# Sheet2.net
KiCad netlist of a schematic drawn in Altium Designer
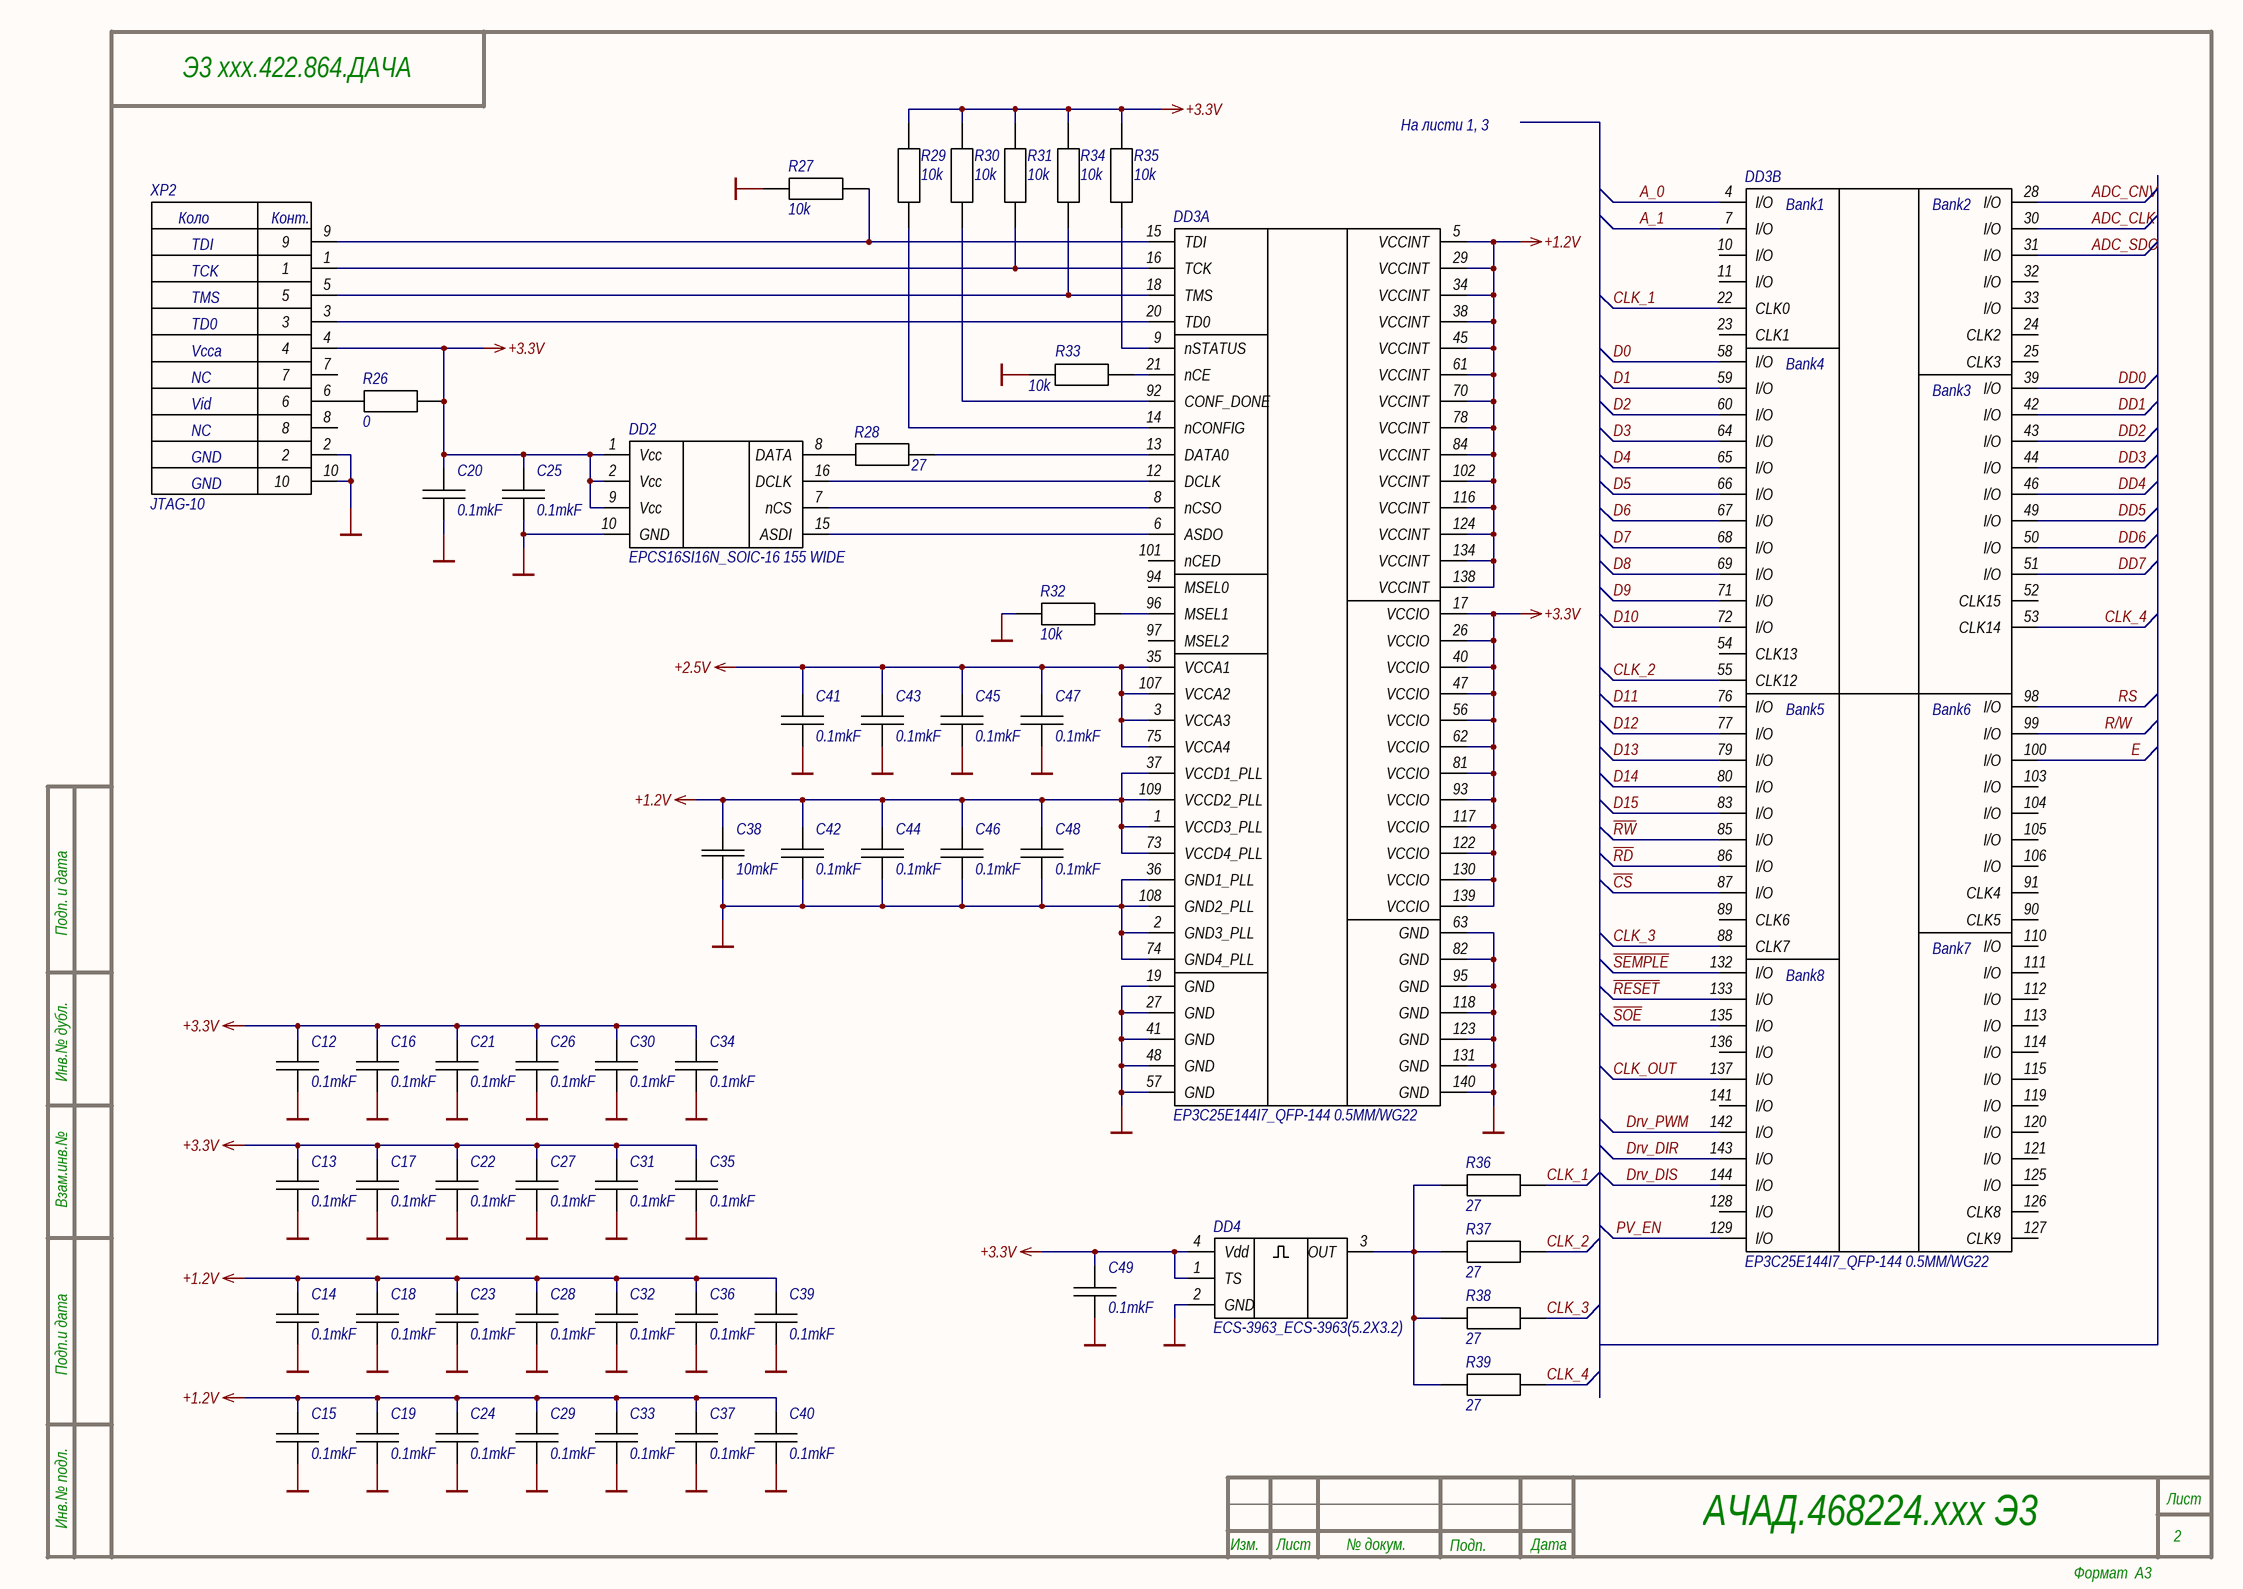
[diagram p0: Sheet2.SchDoc]

(export (version "E")
  (design (tool "Eeschema 10.0.6"))
  (components
    (comp (ref "C12")
      (value "0.1mkF")
      (footprint "C_0603")
      (description "C_0.1mkF_0603")
      (libsource (lib "АСК_1") (part "C_0.1mkF_0603"))
    )
    (comp (ref "C13")
      (value "0.1mkF")
      (footprint "C_0603")
      (description "C_0.1mkF_0603")
      (libsource (lib "АСК_1") (part "C_0.1mkF_0603"))
    )
    (comp (ref "C14")
      (value "0.1mkF")
      (footprint "C_0603")
      (description "C_0.1mkF_0603")
      (libsource (lib "АСК_1") (part "C_0.1mkF_0603"))
    )
    (comp (ref "C15")
      (value "0.1mkF")
      (footprint "C_0603")
      (description "C_0.1mkF_0603")
      (libsource (lib "АСК_1") (part "C_0.1mkF_0603"))
    )
    (comp (ref "C16")
      (value "0.1mkF")
      (footprint "C_0603")
      (description "C_0.1mkF_0603")
      (libsource (lib "АСК_1") (part "C_0.1mkF_0603"))
    )
    (comp (ref "C17")
      (value "0.1mkF")
      (footprint "C_0603")
      (description "C_0.1mkF_0603")
      (libsource (lib "АСК_1") (part "C_0.1mkF_0603"))
    )
    (comp (ref "C18")
      (value "0.1mkF")
      (footprint "C_0603")
      (description "C_0.1mkF_0603")
      (libsource (lib "АСК_1") (part "C_0.1mkF_0603"))
    )
    (comp (ref "C19")
      (value "0.1mkF")
      (footprint "C_0603")
      (description "C_0.1mkF_0603")
      (libsource (lib "АСК_1") (part "C_0.1mkF_0603"))
    )
    (comp (ref "C20")
      (value "0.1mkF")
      (footprint "C_0603")
      (description "C_0.1mkF_0603")
      (libsource (lib "АСК_1") (part "C_0.1mkF_0603"))
    )
    (comp (ref "C21")
      (value "0.1mkF")
      (footprint "C_0603")
      (description "C_0.1mkF_0603")
      (libsource (lib "АСК_1") (part "C_0.1mkF_0603"))
    )
    (comp (ref "C22")
      (value "0.1mkF")
      (footprint "C_0603")
      (description "C_0.1mkF_0603")
      (libsource (lib "АСК_1") (part "C_0.1mkF_0603"))
    )
    (comp (ref "C23")
      (value "0.1mkF")
      (footprint "C_0603")
      (description "C_0.1mkF_0603")
      (libsource (lib "АСК_1") (part "C_0.1mkF_0603"))
    )
    (comp (ref "C24")
      (value "0.1mkF")
      (footprint "C_0603")
      (description "C_0.1mkF_0603")
      (libsource (lib "АСК_1") (part "C_0.1mkF_0603"))
    )
    (comp (ref "C25")
      (value "0.1mkF")
      (footprint "C_0603")
      (description "C_0.1mkF_0603")
      (libsource (lib "АСК_1") (part "C_0.1mkF_0603"))
    )
    (comp (ref "C26")
      (value "0.1mkF")
      (footprint "C_0603")
      (description "C_0.1mkF_0603")
      (libsource (lib "АСК_1") (part "C_0.1mkF_0603"))
    )
    (comp (ref "C27")
      (value "0.1mkF")
      (footprint "C_0603")
      (description "C_0.1mkF_0603")
      (libsource (lib "АСК_1") (part "C_0.1mkF_0603"))
    )
    (comp (ref "C28")
      (value "0.1mkF")
      (footprint "C_0603")
      (description "C_0.1mkF_0603")
      (libsource (lib "АСК_1") (part "C_0.1mkF_0603"))
    )
    (comp (ref "C29")
      (value "0.1mkF")
      (footprint "C_0603")
      (description "C_0.1mkF_0603")
      (libsource (lib "АСК_1") (part "C_0.1mkF_0603"))
    )
    (comp (ref "C30")
      (value "0.1mkF")
      (footprint "C_0603")
      (description "C_0.1mkF_0603")
      (libsource (lib "АСК_1") (part "C_0.1mkF_0603"))
    )
    (comp (ref "C31")
      (value "0.1mkF")
      (footprint "C_0603")
      (description "C_0.1mkF_0603")
      (libsource (lib "АСК_1") (part "C_0.1mkF_0603"))
    )
    (comp (ref "C32")
      (value "0.1mkF")
      (footprint "C_0603")
      (description "C_0.1mkF_0603")
      (libsource (lib "АСК_1") (part "C_0.1mkF_0603"))
    )
    (comp (ref "C33")
      (value "0.1mkF")
      (footprint "C_0603")
      (description "C_0.1mkF_0603")
      (libsource (lib "АСК_1") (part "C_0.1mkF_0603"))
    )
    (comp (ref "C34")
      (value "0.1mkF")
      (footprint "C_0603")
      (description "C_0.1mkF_0603")
      (libsource (lib "АСК_1") (part "C_0.1mkF_0603"))
    )
    (comp (ref "C35")
      (value "0.1mkF")
      (footprint "C_0603")
      (description "C_0.1mkF_0603")
      (libsource (lib "АСК_1") (part "C_0.1mkF_0603"))
    )
    (comp (ref "C36")
      (value "0.1mkF")
      (footprint "C_0603")
      (description "C_0.1mkF_0603")
      (libsource (lib "АСК_1") (part "C_0.1mkF_0603"))
    )
    (comp (ref "C37")
      (value "0.1mkF")
      (footprint "C_0603")
      (description "C_0.1mkF_0603")
      (libsource (lib "АСК_1") (part "C_0.1mkF_0603"))
    )
    (comp (ref "C38")
      (value "10mkF")
      (footprint "C_1206")
      (description "C_10mkF_1206")
      (libsource (lib "АСК_1") (part "C_10mkF_1206"))
    )
    (comp (ref "C39")
      (value "0.1mkF")
      (footprint "C_0603")
      (description "C_0.1mkF_0603")
      (libsource (lib "АСК_1") (part "C_0.1mkF_0603"))
    )
    (comp (ref "C40")
      (value "0.1mkF")
      (footprint "C_0603")
      (description "C_0.1mkF_0603")
      (libsource (lib "АСК_1") (part "C_0.1mkF_0603"))
    )
    (comp (ref "C41")
      (value "0.1mkF")
      (footprint "C_0603")
      (description "C_0.1mkF_0603")
      (libsource (lib "АСК_1") (part "C_0.1mkF_0603"))
    )
    (comp (ref "C42")
      (value "0.1mkF")
      (footprint "C_0603")
      (description "C_0.1mkF_0603")
      (libsource (lib "АСК_1") (part "C_0.1mkF_0603"))
    )
    (comp (ref "C43")
      (value "0.1mkF")
      (footprint "C_0603")
      (description "C_0.1mkF_0603")
      (libsource (lib "АСК_1") (part "C_0.1mkF_0603"))
    )
    (comp (ref "C44")
      (value "0.1mkF")
      (footprint "C_0603")
      (description "C_0.1mkF_0603")
      (libsource (lib "АСК_1") (part "C_0.1mkF_0603"))
    )
    (comp (ref "C45")
      (value "0.1mkF")
      (footprint "C_0603")
      (description "C_0.1mkF_0603")
      (libsource (lib "АСК_1") (part "C_0.1mkF_0603"))
    )
    (comp (ref "C46")
      (value "0.1mkF")
      (footprint "C_0603")
      (description "C_0.1mkF_0603")
      (libsource (lib "АСК_1") (part "C_0.1mkF_0603"))
    )
    (comp (ref "C47")
      (value "0.1mkF")
      (footprint "C_0603")
      (description "C_0.1mkF_0603")
      (libsource (lib "АСК_1") (part "C_0.1mkF_0603"))
    )
    (comp (ref "C48")
      (value "0.1mkF")
      (footprint "C_0603")
      (description "C_0.1mkF_0603")
      (libsource (lib "АСК_1") (part "C_0.1mkF_0603"))
    )
    (comp (ref "C49")
      (value "0.1mkF")
      (footprint "C_0603")
      (description "C_0.1mkF_0603")
      (libsource (lib "АСК_1") (part "C_0.1mkF_0603"))
    )
    (comp (ref "DD2")
      (value "EPCS16SI16N_SOIC-16 155 WIDE")
      (footprint "SOIC127P600X175-16N")
      (libsource (lib "АСК_1") (part "EPCS16SI16N_SOIC-16 155 WIDE"))
    )
    (comp (ref "DD3")
      (value "EP3C25E144I7_QFP-144 0.5MM/WG22")
      (footprint "QFP65P3122X3122X395-144N")
      (libsource (lib "АСК_1") (part "EP3C25E144I7_QFP-144 0.5MM/WG22"))
    )
    (comp (ref "DD4")
      (value "ECS-3963_ECS-3963(5.2X3.2)")
      (footprint "ECS-3961")
      (libsource (lib "АСК_1") (part "ECS-3963_ECS-3963(5.2X3.2)"))
    )
    (comp (ref "R26")
      (value "0")
      (footprint "R_1206")
      (description "R_10_1206")
      (libsource (lib "АСК_1") (part "R_10_1206"))
    )
    (comp (ref "R27")
      (value "10k")
      (footprint "R_0603")
      (description "R_10k_0603")
      (libsource (lib "АСК_1") (part "R_10k_0603"))
    )
    (comp (ref "R28")
      (value "27")
      (footprint "R_1206")
      (description "R_10_1206")
      (libsource (lib "АСК_1") (part "R_10_1206"))
    )
    (comp (ref "R29")
      (value "10k")
      (footprint "R_0603")
      (description "R_10k_0603")
      (libsource (lib "АСК_1") (part "R_10k_0603"))
    )
    (comp (ref "R30")
      (value "10k")
      (footprint "R_0603")
      (description "R_10k_0603")
      (libsource (lib "АСК_1") (part "R_10k_0603"))
    )
    (comp (ref "R31")
      (value "10k")
      (footprint "R_0603")
      (description "R_10k_0603")
      (libsource (lib "АСК_1") (part "R_10k_0603"))
    )
    (comp (ref "R32")
      (value "10k")
      (footprint "R_0603")
      (description "R_10k_0603")
      (libsource (lib "АСК_1") (part "R_10k_0603"))
    )
    (comp (ref "R33")
      (value "10k")
      (footprint "R_0603")
      (description "R_10k_0603")
      (libsource (lib "АСК_1") (part "R_10k_0603"))
    )
    (comp (ref "R34")
      (value "10k")
      (footprint "R_0603")
      (description "R_10k_0603")
      (libsource (lib "АСК_1") (part "R_10k_0603"))
    )
    (comp (ref "R35")
      (value "10k")
      (footprint "R_0603")
      (description "R_10k_0603")
      (libsource (lib "АСК_1") (part "R_10k_0603"))
    )
    (comp (ref "R36")
      (value "27")
      (footprint "R_0603")
      (description "R_10k_0603")
      (libsource (lib "АСК_1") (part "R_10k_0603"))
    )
    (comp (ref "R37")
      (value "27")
      (footprint "R_0603")
      (description "R_10k_0603")
      (libsource (lib "АСК_1") (part "R_10k_0603"))
    )
    (comp (ref "R38")
      (value "27")
      (footprint "R_0603")
      (description "R_10k_0603")
      (libsource (lib "АСК_1") (part "R_10k_0603"))
    )
    (comp (ref "R39")
      (value "27")
      (footprint "R_0603")
      (description "R_10k_0603")
      (libsource (lib "АСК_1") (part "R_10k_0603"))
    )
    (comp (ref "XP2") (value "JTAG-10") (libsource (lib "АСК_1") (part "JTAG-10")))
  )
  (nets
    (net (code "1") (name "+1.2V") (class "Default")
      (node (ref "C14") (pin "2") (pinfunction "2_2") (pintype "passive"))
      (node (ref "C15") (pin "2") (pinfunction "2_2") (pintype "passive"))
      (node (ref "C18") (pin "2") (pinfunction "2_2") (pintype "passive"))
      (node (ref "C19") (pin "2") (pinfunction "2_2") (pintype "passive"))
      (node (ref "C23") (pin "2") (pinfunction "2_2") (pintype "passive"))
      (node (ref "C24") (pin "2") (pinfunction "2_2") (pintype "passive"))
      (node (ref "C28") (pin "2") (pinfunction "2_2") (pintype "passive"))
      (node (ref "C29") (pin "2") (pinfunction "2_2") (pintype "passive"))
      (node (ref "C32") (pin "2") (pinfunction "2_2") (pintype "passive"))
      (node (ref "C33") (pin "2") (pinfunction "2_2") (pintype "passive"))
      (node (ref "C36") (pin "2") (pinfunction "2_2") (pintype "passive"))
      (node (ref "C37") (pin "2") (pinfunction "2_2") (pintype "passive"))
      (node (ref "C38") (pin "2") (pinfunction "2_2") (pintype "passive"))
      (node (ref "C39") (pin "2") (pinfunction "2_2") (pintype "passive"))
      (node (ref "C40") (pin "2") (pinfunction "2_2") (pintype "passive"))
      (node (ref "C42") (pin "2") (pinfunction "2_2") (pintype "passive"))
      (node (ref "C44") (pin "2") (pinfunction "2_2") (pintype "passive"))
      (node (ref "C46") (pin "2") (pinfunction "2_2") (pintype "passive"))
      (node (ref "C48") (pin "2") (pinfunction "2_2") (pintype "passive"))
      (node (ref "DD3") (pin "1") (pinfunction "VCCD3_PLL_1") (pintype "passive"))
      (node (ref "DD3") (pin "102") (pinfunction "VCCINT_102") (pintype "passive"))
      (node (ref "DD3") (pin "109") (pinfunction "VCCD2_PLL_109") (pintype "passive"))
      (node (ref "DD3") (pin "116") (pinfunction "VCCINT_116") (pintype "passive"))
      (node (ref "DD3") (pin "124") (pinfunction "VCCINT_124") (pintype "passive"))
      (node (ref "DD3") (pin "134") (pinfunction "VCCINT_134") (pintype "passive"))
      (node (ref "DD3") (pin "138") (pinfunction "VCCINT_138") (pintype "passive"))
      (node (ref "DD3") (pin "29") (pinfunction "VCCINT_29") (pintype "passive"))
      (node (ref "DD3") (pin "34") (pinfunction "VCCINT_34") (pintype "passive"))
      (node (ref "DD3") (pin "37") (pinfunction "VCCD1_PLL_37") (pintype "passive"))
      (node (ref "DD3") (pin "38") (pinfunction "VCCINT_38") (pintype "passive"))
      (node (ref "DD3") (pin "45") (pinfunction "VCCINT_45") (pintype "passive"))
      (node (ref "DD3") (pin "5") (pinfunction "VCCINT_5") (pintype "passive"))
      (node (ref "DD3") (pin "61") (pinfunction "VCCINT_61") (pintype "passive"))
      (node (ref "DD3") (pin "70") (pinfunction "VCCINT_70") (pintype "passive"))
      (node (ref "DD3") (pin "73") (pinfunction "VCCD4_PLL_73") (pintype "passive"))
      (node (ref "DD3") (pin "78") (pinfunction "VCCINT_78") (pintype "passive"))
      (node (ref "DD3") (pin "84") (pinfunction "VCCINT_84") (pintype "passive"))
    )
    (net (code "2") (name "+2.5V") (class "Default")
      (node (ref "C41") (pin "2") (pinfunction "2_2") (pintype "passive"))
      (node (ref "C43") (pin "2") (pinfunction "2_2") (pintype "passive"))
      (node (ref "C45") (pin "2") (pinfunction "2_2") (pintype "passive"))
      (node (ref "C47") (pin "2") (pinfunction "2_2") (pintype "passive"))
      (node (ref "DD3") (pin "107") (pinfunction "VCCA2_107") (pintype "passive"))
      (node (ref "DD3") (pin "3") (pinfunction "VCCA3_3") (pintype "passive"))
      (node (ref "DD3") (pin "35") (pinfunction "VCCA1_35") (pintype "passive"))
      (node (ref "DD3") (pin "75") (pinfunction "VCCA4_75") (pintype "passive"))
    )
    (net (code "3") (name "+3.3V") (class "Default")
      (node (ref "C12") (pin "2") (pinfunction "2_2") (pintype "passive"))
      (node (ref "C13") (pin "2") (pinfunction "2_2") (pintype "passive"))
      (node (ref "C16") (pin "2") (pinfunction "2_2") (pintype "passive"))
      (node (ref "C17") (pin "2") (pinfunction "2_2") (pintype "passive"))
      (node (ref "C20") (pin "2") (pinfunction "2_2") (pintype "passive"))
      (node (ref "C21") (pin "2") (pinfunction "2_2") (pintype "passive"))
      (node (ref "C22") (pin "2") (pinfunction "2_2") (pintype "passive"))
      (node (ref "C25") (pin "2") (pinfunction "2_2") (pintype "passive"))
      (node (ref "C26") (pin "2") (pinfunction "2_2") (pintype "passive"))
      (node (ref "C27") (pin "2") (pinfunction "2_2") (pintype "passive"))
      (node (ref "C30") (pin "2") (pinfunction "2_2") (pintype "passive"))
      (node (ref "C31") (pin "2") (pinfunction "2_2") (pintype "passive"))
      (node (ref "C34") (pin "2") (pinfunction "2_2") (pintype "passive"))
      (node (ref "C35") (pin "2") (pinfunction "2_2") (pintype "passive"))
      (node (ref "C49") (pin "2") (pinfunction "2_2") (pintype "passive"))
      (node (ref "DD2") (pin "1") (pinfunction "Vcc_1") (pintype "passive"))
      (node (ref "DD2") (pin "2") (pinfunction "Vcc_2") (pintype "passive"))
      (node (ref "DD2") (pin "9") (pinfunction "Vcc_9") (pintype "passive"))
      (node (ref "DD3") (pin "117") (pinfunction "VCCIO_117") (pintype "passive"))
      (node (ref "DD3") (pin "122") (pinfunction "VCCIO_122") (pintype "passive"))
      (node (ref "DD3") (pin "130") (pinfunction "VCCIO_130") (pintype "passive"))
      (node (ref "DD3") (pin "139") (pinfunction "VCCIO_139") (pintype "passive"))
      (node (ref "DD3") (pin "17") (pinfunction "VCCIO_17") (pintype "passive"))
      (node (ref "DD3") (pin "26") (pinfunction "VCCIO_26") (pintype "passive"))
      (node (ref "DD3") (pin "40") (pinfunction "VCCIO_40") (pintype "passive"))
      (node (ref "DD3") (pin "47") (pinfunction "VCCIO_47") (pintype "passive"))
      (node (ref "DD3") (pin "56") (pinfunction "VCCIO_56") (pintype "passive"))
      (node (ref "DD3") (pin "62") (pinfunction "VCCIO_62") (pintype "passive"))
      (node (ref "DD3") (pin "81") (pinfunction "VCCIO_81") (pintype "passive"))
      (node (ref "DD3") (pin "93") (pinfunction "VCCIO_93") (pintype "passive"))
      (node (ref "DD4") (pin "1") (pinfunction "TS_1") (pintype "passive"))
      (node (ref "DD4") (pin "4") (pinfunction "Vdd_4") (pintype "passive"))
      (node (ref "R26") (pin "1") (pinfunction "1_1") (pintype "passive"))
      (node (ref "R29") (pin "2") (pinfunction "2_2") (pintype "passive"))
      (node (ref "R30") (pin "2") (pinfunction "2_2") (pintype "passive"))
      (node (ref "R31") (pin "2") (pinfunction "2_2") (pintype "passive"))
      (node (ref "R34") (pin "2") (pinfunction "2_2") (pintype "passive"))
      (node (ref "R35") (pin "2") (pinfunction "2_2") (pintype "passive"))
      (node (ref "XP2") (pin "4") (pinfunction "4_4") (pintype "passive"))
    )
    (net (code "4") (name "/ADC_CLK") (class "Default")
      (node (ref "DD3") (pin "30") (pinfunction "I/O_30") (pintype "passive"))
    )
    (net (code "5") (name "/ADC_CNV") (class "Default")
      (node (ref "DD3") (pin "28") (pinfunction "I/O_28") (pintype "passive"))
    )
    (net (code "6") (name "/ADC_SDO") (class "Default")
      (node (ref "DD3") (pin "31") (pinfunction "I/O_31") (pintype "passive"))
    )
    (net (code "7") (name "/A_0") (class "Default")
      (node (ref "DD3") (pin "4") (pinfunction "I/O_4") (pintype "passive"))
    )
    (net (code "8") (name "/A_1") (class "Default")
      (node (ref "DD3") (pin "7") (pinfunction "I/O_7") (pintype "passive"))
    )
    (net (code "9") (name "/CLK_1") (class "Default")
      (node (ref "DD3") (pin "22") (pinfunction "CLK0_22") (pintype "passive"))
      (node (ref "R36") (pin "2") (pinfunction "2_2") (pintype "passive"))
    )
    (net (code "10") (name "/CLK_2") (class "Default")
      (node (ref "DD3") (pin "55") (pinfunction "CLK12_55") (pintype "passive"))
      (node (ref "R37") (pin "2") (pinfunction "2_2") (pintype "passive"))
    )
    (net (code "11") (name "/CLK_3") (class "Default")
      (node (ref "DD3") (pin "88") (pinfunction "CLK7_88") (pintype "passive"))
      (node (ref "R38") (pin "2") (pinfunction "2_2") (pintype "passive"))
    )
    (net (code "12") (name "/CLK_4") (class "Default")
      (node (ref "DD3") (pin "53") (pinfunction "CLK14_53") (pintype "passive"))
      (node (ref "R39") (pin "2") (pinfunction "2_2") (pintype "passive"))
    )
    (net (code "13") (name "/CLK_OUT") (class "Default")
      (node (ref "DD3") (pin "137") (pinfunction "I/O_137") (pintype "passive"))
    )
    (net (code "14") (name "/D0") (class "Default")
      (node (ref "DD3") (pin "58") (pinfunction "I/O_58") (pintype "passive"))
    )
    (net (code "15") (name "/D1") (class "Default")
      (node (ref "DD3") (pin "59") (pinfunction "I/O_59") (pintype "passive"))
    )
    (net (code "16") (name "/D2") (class "Default")
      (node (ref "DD3") (pin "60") (pinfunction "I/O_60") (pintype "passive"))
    )
    (net (code "17") (name "/D3") (class "Default")
      (node (ref "DD3") (pin "64") (pinfunction "I/O_64") (pintype "passive"))
    )
    (net (code "18") (name "/D4") (class "Default")
      (node (ref "DD3") (pin "65") (pinfunction "I/O_65") (pintype "passive"))
    )
    (net (code "19") (name "/D5") (class "Default")
      (node (ref "DD3") (pin "66") (pinfunction "I/O_66") (pintype "passive"))
    )
    (net (code "20") (name "/D6") (class "Default")
      (node (ref "DD3") (pin "67") (pinfunction "I/O_67") (pintype "passive"))
    )
    (net (code "21") (name "/D7") (class "Default")
      (node (ref "DD3") (pin "68") (pinfunction "I/O_68") (pintype "passive"))
    )
    (net (code "22") (name "/D8") (class "Default")
      (node (ref "DD3") (pin "69") (pinfunction "I/O_69") (pintype "passive"))
    )
    (net (code "23") (name "/D9") (class "Default")
      (node (ref "DD3") (pin "71") (pinfunction "I/O_71") (pintype "passive"))
    )
    (net (code "24") (name "/D10") (class "Default")
      (node (ref "DD3") (pin "72") (pinfunction "I/O_72") (pintype "passive"))
    )
    (net (code "25") (name "/D11") (class "Default")
      (node (ref "DD3") (pin "76") (pinfunction "I/O_76") (pintype "passive"))
    )
    (net (code "26") (name "/D12") (class "Default")
      (node (ref "DD3") (pin "77") (pinfunction "I/O_77") (pintype "passive"))
    )
    (net (code "27") (name "/D13") (class "Default")
      (node (ref "DD3") (pin "79") (pinfunction "I/O_79") (pintype "passive"))
    )
    (net (code "28") (name "/D14") (class "Default")
      (node (ref "DD3") (pin "80") (pinfunction "I/O_80") (pintype "passive"))
    )
    (net (code "29") (name "/D15") (class "Default")
      (node (ref "DD3") (pin "83") (pinfunction "I/O_83") (pintype "passive"))
    )
    (net (code "30") (name "/DD0") (class "Default")
      (node (ref "DD3") (pin "39") (pinfunction "I/O_39") (pintype "passive"))
    )
    (net (code "31") (name "/DD1") (class "Default")
      (node (ref "DD3") (pin "42") (pinfunction "I/O_42") (pintype "passive"))
    )
    (net (code "32") (name "/DD2") (class "Default")
      (node (ref "DD3") (pin "43") (pinfunction "I/O_43") (pintype "passive"))
    )
    (net (code "33") (name "/DD3") (class "Default")
      (node (ref "DD3") (pin "44") (pinfunction "I/O_44") (pintype "passive"))
    )
    (net (code "34") (name "/DD4") (class "Default")
      (node (ref "DD3") (pin "46") (pinfunction "I/O_46") (pintype "passive"))
    )
    (net (code "35") (name "/DD5") (class "Default")
      (node (ref "DD3") (pin "49") (pinfunction "I/O_49") (pintype "passive"))
    )
    (net (code "36") (name "/DD6") (class "Default")
      (node (ref "DD3") (pin "50") (pinfunction "I/O_50") (pintype "passive"))
    )
    (net (code "37") (name "/DD7") (class "Default")
      (node (ref "DD3") (pin "51") (pinfunction "I/O_51") (pintype "passive"))
    )
    (net (code "38") (name "/Drv_DIR") (class "Default")
      (node (ref "DD3") (pin "143") (pinfunction "I/O_143") (pintype "passive"))
    )
    (net (code "39") (name "/Drv_DIS") (class "Default")
      (node (ref "DD3") (pin "144") (pinfunction "I/O_144") (pintype "passive"))
    )
    (net (code "40") (name "/Drv_PWM") (class "Default")
      (node (ref "DD3") (pin "142") (pinfunction "I/O_142") (pintype "passive"))
    )
    (net (code "41") (name "/E") (class "Default")
      (node (ref "DD3") (pin "100") (pinfunction "I/O_100") (pintype "passive"))
    )
    (net (code "42") (name "/PV_EN") (class "Default")
      (node (ref "DD3") (pin "129") (pinfunction "I/O_129") (pintype "passive"))
    )
    (net (code "43") (name "/RS") (class "Default")
      (node (ref "DD3") (pin "98") (pinfunction "I/O_98") (pintype "passive"))
    )
    (net (code "44") (name "/R{slash}W") (class "Default")
      (node (ref "DD3") (pin "99") (pinfunction "I/O_99") (pintype "passive"))
    )
    (net (code "45") (name "/~{CS}") (class "Default")
      (node (ref "DD3") (pin "87") (pinfunction "I/O_87") (pintype "passive"))
    )
    (net (code "46") (name "/~{RD}") (class "Default")
      (node (ref "DD3") (pin "86") (pinfunction "I/O_86") (pintype "passive"))
    )
    (net (code "47") (name "/~{RESET}") (class "Default")
      (node (ref "DD3") (pin "133") (pinfunction "I/O_133") (pintype "passive"))
    )
    (net (code "48") (name "/~{RW}") (class "Default")
      (node (ref "DD3") (pin "85") (pinfunction "I/O_85") (pintype "passive"))
    )
    (net (code "49") (name "/~{SEMPLE}") (class "Default")
      (node (ref "DD3") (pin "132") (pinfunction "I/O_132") (pintype "passive"))
    )
    (net (code "50") (name "/~{SOE}") (class "Default")
      (node (ref "DD3") (pin "135") (pinfunction "I/O_135") (pintype "passive"))
    )
    (net (code "51") (name "GND") (class "Default")
      (node (ref "C12") (pin "1") (pinfunction "1_1") (pintype "passive"))
      (node (ref "C13") (pin "1") (pinfunction "1_1") (pintype "passive"))
      (node (ref "C14") (pin "1") (pinfunction "1_1") (pintype "passive"))
      (node (ref "C15") (pin "1") (pinfunction "1_1") (pintype "passive"))
      (node (ref "C16") (pin "1") (pinfunction "1_1") (pintype "passive"))
      (node (ref "C17") (pin "1") (pinfunction "1_1") (pintype "passive"))
      (node (ref "C18") (pin "1") (pinfunction "1_1") (pintype "passive"))
      (node (ref "C19") (pin "1") (pinfunction "1_1") (pintype "passive"))
      (node (ref "C20") (pin "1") (pinfunction "1_1") (pintype "passive"))
      (node (ref "C21") (pin "1") (pinfunction "1_1") (pintype "passive"))
      (node (ref "C22") (pin "1") (pinfunction "1_1") (pintype "passive"))
      (node (ref "C23") (pin "1") (pinfunction "1_1") (pintype "passive"))
      (node (ref "C24") (pin "1") (pinfunction "1_1") (pintype "passive"))
      (node (ref "C25") (pin "1") (pinfunction "1_1") (pintype "passive"))
      (node (ref "C26") (pin "1") (pinfunction "1_1") (pintype "passive"))
      (node (ref "C27") (pin "1") (pinfunction "1_1") (pintype "passive"))
      (node (ref "C28") (pin "1") (pinfunction "1_1") (pintype "passive"))
      (node (ref "C29") (pin "1") (pinfunction "1_1") (pintype "passive"))
      (node (ref "C30") (pin "1") (pinfunction "1_1") (pintype "passive"))
      (node (ref "C31") (pin "1") (pinfunction "1_1") (pintype "passive"))
      (node (ref "C32") (pin "1") (pinfunction "1_1") (pintype "passive"))
      (node (ref "C33") (pin "1") (pinfunction "1_1") (pintype "passive"))
      (node (ref "C34") (pin "1") (pinfunction "1_1") (pintype "passive"))
      (node (ref "C35") (pin "1") (pinfunction "1_1") (pintype "passive"))
      (node (ref "C36") (pin "1") (pinfunction "1_1") (pintype "passive"))
      (node (ref "C37") (pin "1") (pinfunction "1_1") (pintype "passive"))
      (node (ref "C38") (pin "1") (pinfunction "1_1") (pintype "passive"))
      (node (ref "C39") (pin "1") (pinfunction "1_1") (pintype "passive"))
      (node (ref "C40") (pin "1") (pinfunction "1_1") (pintype "passive"))
      (node (ref "C41") (pin "1") (pinfunction "1_1") (pintype "passive"))
      (node (ref "C42") (pin "1") (pinfunction "1_1") (pintype "passive"))
      (node (ref "C43") (pin "1") (pinfunction "1_1") (pintype "passive"))
      (node (ref "C44") (pin "1") (pinfunction "1_1") (pintype "passive"))
      (node (ref "C45") (pin "1") (pinfunction "1_1") (pintype "passive"))
      (node (ref "C46") (pin "1") (pinfunction "1_1") (pintype "passive"))
      (node (ref "C47") (pin "1") (pinfunction "1_1") (pintype "passive"))
      (node (ref "C48") (pin "1") (pinfunction "1_1") (pintype "passive"))
      (node (ref "C49") (pin "1") (pinfunction "1_1") (pintype "passive"))
      (node (ref "DD2") (pin "10") (pinfunction "GND_10") (pintype "passive"))
      (node (ref "DD3") (pin "108") (pinfunction "GND2_PLL_108") (pintype "passive"))
      (node (ref "DD3") (pin "118") (pinfunction "GND_118") (pintype "passive"))
      (node (ref "DD3") (pin "123") (pinfunction "GND_123") (pintype "passive"))
      (node (ref "DD3") (pin "131") (pinfunction "GND_131") (pintype "passive"))
      (node (ref "DD3") (pin "140") (pinfunction "GND_140") (pintype "passive"))
      (node (ref "DD3") (pin "19") (pinfunction "GND_19") (pintype "passive"))
      (node (ref "DD3") (pin "2") (pinfunction "GND3_PLL_2") (pintype "passive"))
      (node (ref "DD3") (pin "27") (pinfunction "GND_27") (pintype "passive"))
      (node (ref "DD3") (pin "36") (pinfunction "GND1_PLL_36") (pintype "passive"))
      (node (ref "DD3") (pin "41") (pinfunction "GND_41") (pintype "passive"))
      (node (ref "DD3") (pin "48") (pinfunction "GND_48") (pintype "passive"))
      (node (ref "DD3") (pin "57") (pinfunction "GND_57") (pintype "passive"))
      (node (ref "DD3") (pin "63") (pinfunction "GND_63") (pintype "passive"))
      (node (ref "DD3") (pin "74") (pinfunction "GND4_PLL_74") (pintype "passive"))
      (node (ref "DD3") (pin "82") (pinfunction "GND_82") (pintype "passive"))
      (node (ref "DD3") (pin "95") (pinfunction "GND_95") (pintype "passive"))
      (node (ref "DD4") (pin "2") (pinfunction "GND_2") (pintype "passive"))
      (node (ref "R27") (pin "1") (pinfunction "1_1") (pintype "passive"))
      (node (ref "R32") (pin "1") (pinfunction "1_1") (pintype "passive"))
      (node (ref "R33") (pin "1") (pinfunction "1_1") (pintype "passive"))
      (node (ref "XP2") (pin "10") (pinfunction "10_10") (pintype "passive"))
      (node (ref "XP2") (pin "2") (pinfunction "2_2") (pintype "passive"))
    )
    (net (code "52") (name "Net-(DD2-ASDI)") (class "Default")
      (node (ref "DD2") (pin "15") (pinfunction "ASDI_15") (pintype "passive"))
      (node (ref "DD3") (pin "6") (pinfunction "ASDO_6") (pintype "passive"))
    )
    (net (code "53") (name "Net-(DD2-DATA)") (class "Default")
      (node (ref "DD2") (pin "8") (pinfunction "DATA_8") (pintype "passive"))
      (node (ref "R28") (pin "1") (pinfunction "1_1") (pintype "passive"))
    )
    (net (code "54") (name "Net-(DD2-DCLK)") (class "Default")
      (node (ref "DD2") (pin "16") (pinfunction "DCLK_16") (pintype "passive"))
      (node (ref "DD3") (pin "12") (pinfunction "DCLK_12") (pintype "passive"))
    )
    (net (code "55") (name "Net-(DD2-nCS)") (class "Default")
      (node (ref "DD2") (pin "7") (pinfunction "nCS_7") (pintype "passive"))
      (node (ref "DD3") (pin "8") (pinfunction "nCSO_8") (pintype "passive"))
    )
    (net (code "56") (name "Net-(DD3A-CONF_DONE)") (class "Default")
      (node (ref "DD3") (pin "92") (pinfunction "CONF_DONE_92") (pintype "passive"))
      (node (ref "R30") (pin "1") (pinfunction "1_1") (pintype "passive"))
    )
    (net (code "57") (name "Net-(DD3A-DATA0)") (class "Default")
      (node (ref "DD3") (pin "13") (pinfunction "DATA0_13") (pintype "passive"))
      (node (ref "R28") (pin "2") (pinfunction "2_2") (pintype "passive"))
    )
    (net (code "58") (name "Net-(DD3A-MSEL1)") (class "Default")
      (node (ref "DD3") (pin "96") (pinfunction "MSEL1_96") (pintype "passive"))
      (node (ref "R32") (pin "2") (pinfunction "2_2") (pintype "passive"))
    )
    (net (code "59") (name "Net-(DD3A-TCK)") (class "Default")
      (node (ref "DD3") (pin "16") (pinfunction "TCK_16") (pintype "passive"))
      (node (ref "R31") (pin "1") (pinfunction "1_1") (pintype "passive"))
      (node (ref "XP2") (pin "1") (pinfunction "1_1") (pintype "passive"))
    )
    (net (code "60") (name "Net-(DD3A-TD0)") (class "Default")
      (node (ref "DD3") (pin "20") (pinfunction "TD0_20") (pintype "passive"))
      (node (ref "XP2") (pin "3") (pinfunction "3_3") (pintype "passive"))
    )
    (net (code "61") (name "Net-(DD3A-TDI)") (class "Default")
      (node (ref "DD3") (pin "15") (pinfunction "TDI_15") (pintype "passive"))
      (node (ref "R27") (pin "2") (pinfunction "2_2") (pintype "passive"))
      (node (ref "XP2") (pin "9") (pinfunction "9_9") (pintype "passive"))
    )
    (net (code "62") (name "Net-(DD3A-TMS)") (class "Default")
      (node (ref "DD3") (pin "18") (pinfunction "TMS_18") (pintype "passive"))
      (node (ref "R34") (pin "1") (pinfunction "1_1") (pintype "passive"))
      (node (ref "XP2") (pin "5") (pinfunction "5_5") (pintype "passive"))
    )
    (net (code "63") (name "Net-(DD3A-nCE)") (class "Default")
      (node (ref "DD3") (pin "21") (pinfunction "nCE_21") (pintype "passive"))
      (node (ref "R33") (pin "2") (pinfunction "2_2") (pintype "passive"))
    )
    (net (code "64") (name "Net-(DD3A-nCONFIG)") (class "Default")
      (node (ref "DD3") (pin "14") (pinfunction "nCONFIG_14") (pintype "passive"))
      (node (ref "R29") (pin "1") (pinfunction "1_1") (pintype "passive"))
    )
    (net (code "65") (name "Net-(DD3A-nSTATUS)") (class "Default")
      (node (ref "DD3") (pin "9") (pinfunction "nSTATUS_9") (pintype "passive"))
      (node (ref "R35") (pin "1") (pinfunction "1_1") (pintype "passive"))
    )
    (net (code "66") (name "Net-(DD4-OUT)") (class "Default")
      (node (ref "DD4") (pin "3") (pinfunction "OUT_3") (pintype "passive"))
      (node (ref "R36") (pin "1") (pinfunction "1_1") (pintype "passive"))
      (node (ref "R37") (pin "1") (pinfunction "1_1") (pintype "passive"))
      (node (ref "R38") (pin "1") (pinfunction "1_1") (pintype "passive"))
      (node (ref "R39") (pin "1") (pinfunction "1_1") (pintype "passive"))
    )
    (net (code "67") (name "Net-(R26-Pad2)") (class "Default")
      (node (ref "R26") (pin "2") (pinfunction "2_2") (pintype "passive"))
      (node (ref "XP2") (pin "6") (pinfunction "6_6") (pintype "passive"))
    )
    (net (code "68") (name "unconnected-(DD3A-MSEL0-Pad94)") (class "Default")
      (node (ref "DD3") (pin "94") (pinfunction "MSEL0_94") (pintype "passive"))
    )
    (net (code "69") (name "unconnected-(DD3A-MSEL2-Pad97)") (class "Default")
      (node (ref "DD3") (pin "97") (pinfunction "MSEL2_97") (pintype "passive"))
    )
    (net (code "70") (name "unconnected-(DD3A-nCED-Pad101)") (class "Default")
      (node (ref "DD3") (pin "101") (pinfunction "nCED_101") (pintype "passive"))
    )
    (net (code "71") (name "unconnected-(DD3B-CLK1-Pad23)") (class "Default")
      (node (ref "DD3") (pin "23") (pinfunction "CLK1_23") (pintype "passive"))
    )
    (net (code "72") (name "unconnected-(DD3B-CLK2-Pad24)") (class "Default")
      (node (ref "DD3") (pin "24") (pinfunction "CLK2_24") (pintype "passive"))
    )
    (net (code "73") (name "unconnected-(DD3B-CLK3-Pad25)") (class "Default")
      (node (ref "DD3") (pin "25") (pinfunction "CLK3_25") (pintype "passive"))
    )
    (net (code "74") (name "unconnected-(DD3B-CLK4-Pad91)") (class "Default")
      (node (ref "DD3") (pin "91") (pinfunction "CLK4_91") (pintype "passive"))
    )
    (net (code "75") (name "unconnected-(DD3B-CLK5-Pad90)") (class "Default")
      (node (ref "DD3") (pin "90") (pinfunction "CLK5_90") (pintype "passive"))
    )
    (net (code "76") (name "unconnected-(DD3B-CLK6-Pad89)") (class "Default")
      (node (ref "DD3") (pin "89") (pinfunction "CLK6_89") (pintype "passive"))
    )
    (net (code "77") (name "unconnected-(DD3B-CLK8-Pad126)") (class "Default")
      (node (ref "DD3") (pin "126") (pinfunction "CLK8_126") (pintype "passive"))
    )
    (net (code "78") (name "unconnected-(DD3B-CLK9-Pad127)") (class "Default")
      (node (ref "DD3") (pin "127") (pinfunction "CLK9_127") (pintype "passive"))
    )
    (net (code "79") (name "unconnected-(DD3B-CLK13-Pad54)") (class "Default")
      (node (ref "DD3") (pin "54") (pinfunction "CLK13_54") (pintype "passive"))
    )
    (net (code "80") (name "unconnected-(DD3B-CLK15-Pad52)") (class "Default")
      (node (ref "DD3") (pin "52") (pinfunction "CLK15_52") (pintype "passive"))
    )
    (net (code "81") (name "unconnected-(DD3B-I{slash}O-Pad10)") (class "Default")
      (node (ref "DD3") (pin "10") (pinfunction "I/O_10") (pintype "passive"))
    )
    (net (code "82") (name "unconnected-(DD3B-I{slash}O-Pad11)") (class "Default")
      (node (ref "DD3") (pin "11") (pinfunction "I/O_11") (pintype "passive"))
    )
    (net (code "83") (name "unconnected-(DD3B-I{slash}O-Pad32)") (class "Default")
      (node (ref "DD3") (pin "32") (pinfunction "I/O_32") (pintype "passive"))
    )
    (net (code "84") (name "unconnected-(DD3B-I{slash}O-Pad33)") (class "Default")
      (node (ref "DD3") (pin "33") (pinfunction "I/O_33") (pintype "passive"))
    )
    (net (code "85") (name "unconnected-(DD3B-I{slash}O-Pad103)") (class "Default")
      (node (ref "DD3") (pin "103") (pinfunction "I/O_103") (pintype "passive"))
    )
    (net (code "86") (name "unconnected-(DD3B-I{slash}O-Pad104)") (class "Default")
      (node (ref "DD3") (pin "104") (pinfunction "I/O_104") (pintype "passive"))
    )
    (net (code "87") (name "unconnected-(DD3B-I{slash}O-Pad105)") (class "Default")
      (node (ref "DD3") (pin "105") (pinfunction "I/O_105") (pintype "passive"))
    )
    (net (code "88") (name "unconnected-(DD3B-I{slash}O-Pad106)") (class "Default")
      (node (ref "DD3") (pin "106") (pinfunction "I/O_106") (pintype "passive"))
    )
    (net (code "89") (name "unconnected-(DD3B-I{slash}O-Pad110)") (class "Default")
      (node (ref "DD3") (pin "110") (pinfunction "I/O_110") (pintype "passive"))
    )
    (net (code "90") (name "unconnected-(DD3B-I{slash}O-Pad111)") (class "Default")
      (node (ref "DD3") (pin "111") (pinfunction "I/O_111") (pintype "passive"))
    )
    (net (code "91") (name "unconnected-(DD3B-I{slash}O-Pad112)") (class "Default")
      (node (ref "DD3") (pin "112") (pinfunction "I/O_112") (pintype "passive"))
    )
    (net (code "92") (name "unconnected-(DD3B-I{slash}O-Pad113)") (class "Default")
      (node (ref "DD3") (pin "113") (pinfunction "I/O_113") (pintype "passive"))
    )
    (net (code "93") (name "unconnected-(DD3B-I{slash}O-Pad114)") (class "Default")
      (node (ref "DD3") (pin "114") (pinfunction "I/O_114") (pintype "passive"))
    )
    (net (code "94") (name "unconnected-(DD3B-I{slash}O-Pad115)") (class "Default")
      (node (ref "DD3") (pin "115") (pinfunction "I/O_115") (pintype "passive"))
    )
    (net (code "95") (name "unconnected-(DD3B-I{slash}O-Pad119)") (class "Default")
      (node (ref "DD3") (pin "119") (pinfunction "I/O_119") (pintype "passive"))
    )
    (net (code "96") (name "unconnected-(DD3B-I{slash}O-Pad120)") (class "Default")
      (node (ref "DD3") (pin "120") (pinfunction "I/O_120") (pintype "passive"))
    )
    (net (code "97") (name "unconnected-(DD3B-I{slash}O-Pad121)") (class "Default")
      (node (ref "DD3") (pin "121") (pinfunction "I/O_121") (pintype "passive"))
    )
    (net (code "98") (name "unconnected-(DD3B-I{slash}O-Pad125)") (class "Default")
      (node (ref "DD3") (pin "125") (pinfunction "I/O_125") (pintype "passive"))
    )
    (net (code "99") (name "unconnected-(DD3B-I{slash}O-Pad128)") (class "Default")
      (node (ref "DD3") (pin "128") (pinfunction "I/O_128") (pintype "passive"))
    )
    (net (code "100") (name "unconnected-(DD3B-I{slash}O-Pad136)") (class "Default")
      (node (ref "DD3") (pin "136") (pinfunction "I/O_136") (pintype "passive"))
    )
    (net (code "101") (name "unconnected-(DD3B-I{slash}O-Pad141)") (class "Default")
      (node (ref "DD3") (pin "141") (pinfunction "I/O_141") (pintype "passive"))
    )
    (net (code "102") (name "unconnected-(XP2-Pad7)") (class "Default")
      (node (ref "XP2") (pin "7") (pinfunction "7_7") (pintype "passive"))
    )
    (net (code "103") (name "unconnected-(XP2-Pad8)") (class "Default")
      (node (ref "XP2") (pin "8") (pinfunction "8_8") (pintype "passive"))
    )
  )
)
